# testduino.net
KiCad netlist of a schematic drawn in EAGLE
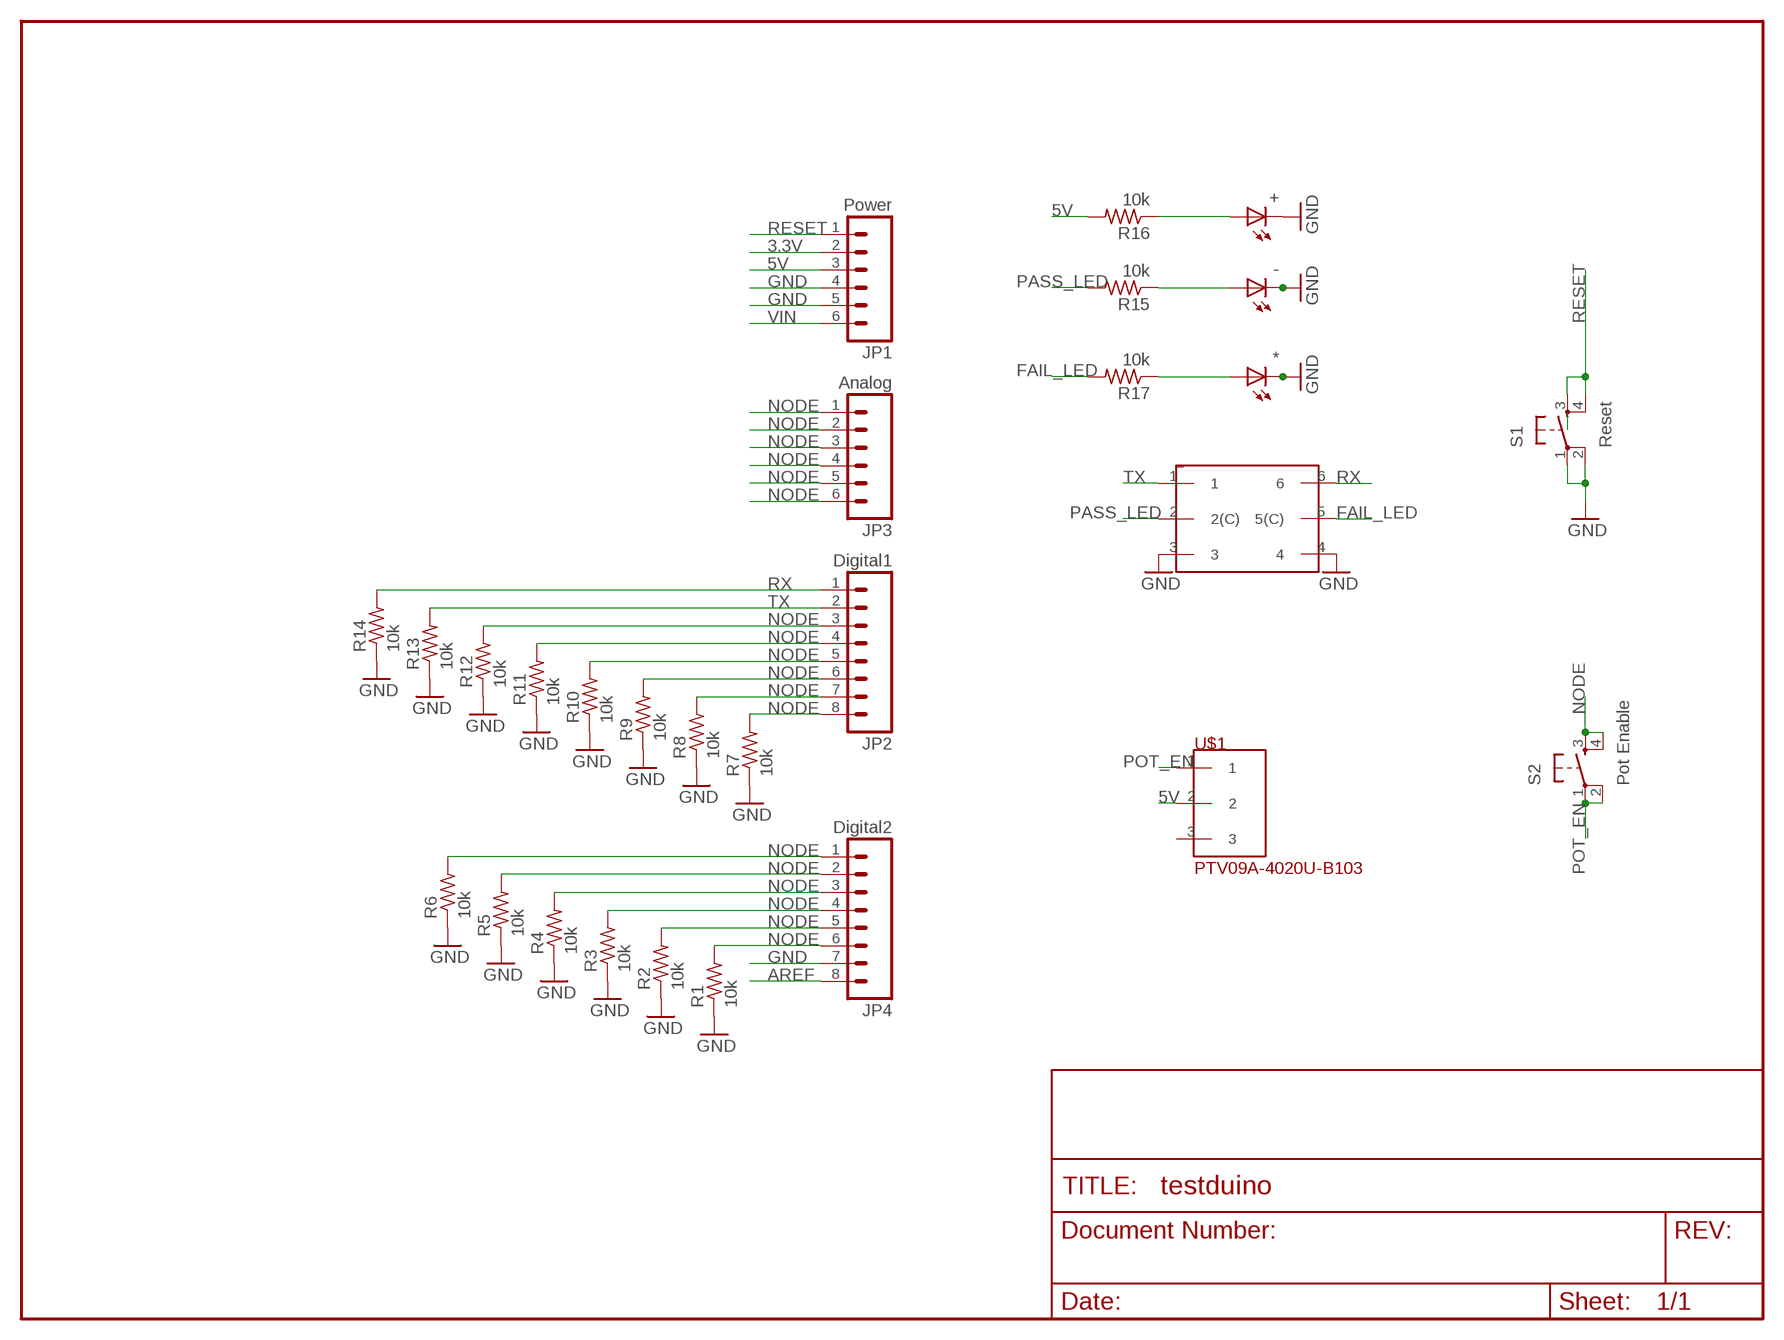
[diagram p0: schematic, sheet 1]

(export (version "E")
  (design (tool "Eeschema 10.0.6"))
  (components
    (comp (ref "*")
      (value "LEDSML0805")
      (footprint "eagle-import:SML0805")
      (libsource (lib "eagle-import") (part "LEDSML0805"))
    )
    (comp (ref "+")
      (value "LEDSML0805")
      (footprint "eagle-import:SML0805")
      (libsource (lib "eagle-import") (part "LEDSML0805"))
    )
    (comp (ref "-")
      (value "LEDSML0805")
      (footprint "eagle-import:SML0805")
      (libsource (lib "eagle-import") (part "LEDSML0805"))
    )
    (comp (ref "JP1")
      (value "Power")
      (footprint "eagle-import:1X06")
      (libsource (lib "eagle-import") (part "M06SIP"))
    )
    (comp (ref "JP2")
      (value "Digital1")
      (footprint "eagle-import:1X08")
      (libsource (lib "eagle-import") (part "M08"))
    )
    (comp (ref "JP3")
      (value "Analog")
      (footprint "eagle-import:1X06")
      (libsource (lib "eagle-import") (part "M06SIP"))
    )
    (comp (ref "JP4")
      (value "Digital2")
      (footprint "eagle-import:1X08")
      (libsource (lib "eagle-import") (part "M08"))
    )
    (comp (ref "R1")
      (value "10k")
      (footprint "eagle-import:R0402")
      (libsource (lib "eagle-import") (part "R-US_R0402"))
    )
    (comp (ref "R2")
      (value "10k")
      (footprint "eagle-import:R0402")
      (libsource (lib "eagle-import") (part "R-US_R0402"))
    )
    (comp (ref "R3")
      (value "10k")
      (footprint "eagle-import:R0402")
      (libsource (lib "eagle-import") (part "R-US_R0402"))
    )
    (comp (ref "R4")
      (value "10k")
      (footprint "eagle-import:R0402")
      (libsource (lib "eagle-import") (part "R-US_R0402"))
    )
    (comp (ref "R5")
      (value "10k")
      (footprint "eagle-import:R0402")
      (libsource (lib "eagle-import") (part "R-US_R0402"))
    )
    (comp (ref "R6")
      (value "10k")
      (footprint "eagle-import:R0402")
      (libsource (lib "eagle-import") (part "R-US_R0402"))
    )
    (comp (ref "R7")
      (value "10k")
      (footprint "eagle-import:R0402")
      (libsource (lib "eagle-import") (part "R-US_R0402"))
    )
    (comp (ref "R8")
      (value "10k")
      (footprint "eagle-import:R0402")
      (libsource (lib "eagle-import") (part "R-US_R0402"))
    )
    (comp (ref "R9")
      (value "10k")
      (footprint "eagle-import:R0402")
      (libsource (lib "eagle-import") (part "R-US_R0402"))
    )
    (comp (ref "R10")
      (value "10k")
      (footprint "eagle-import:R0402")
      (libsource (lib "eagle-import") (part "R-US_R0402"))
    )
    (comp (ref "R11")
      (value "10k")
      (footprint "eagle-import:R0402")
      (libsource (lib "eagle-import") (part "R-US_R0402"))
    )
    (comp (ref "R12")
      (value "10k")
      (footprint "eagle-import:R0402")
      (libsource (lib "eagle-import") (part "R-US_R0402"))
    )
    (comp (ref "R13")
      (value "10k")
      (footprint "eagle-import:R0402")
      (libsource (lib "eagle-import") (part "R-US_R0402"))
    )
    (comp (ref "R14")
      (value "10k")
      (footprint "eagle-import:R0402")
      (libsource (lib "eagle-import") (part "R-US_R0402"))
    )
    (comp (ref "R15")
      (value "10k")
      (footprint "eagle-import:R0402")
      (libsource (lib "eagle-import") (part "R-US_R0402"))
    )
    (comp (ref "R16")
      (value "10k")
      (footprint "eagle-import:R0402")
      (libsource (lib "eagle-import") (part "R-US_R0402"))
    )
    (comp (ref "R17")
      (value "10k")
      (footprint "eagle-import:R0402")
      (libsource (lib "eagle-import") (part "R-US_R0402"))
    )
    (comp (ref "S1")
      (value "Reset")
      (footprint "eagle-import:TACTILE-PTH")
      (libsource (lib "eagle-import") (part "TAC_SWITCHPTH"))
    )
    (comp (ref "S2")
      (value "Pot Enable")
      (footprint "eagle-import:TACTILE-PTH")
      (libsource (lib "eagle-import") (part "TAC_SWITCHPTH"))
    )
    (comp (ref "U$1")
      (value "PTV09A-4020U-B103")
      (footprint "eagle-import:PTV09A-1")
      (libsource (lib "eagle-import") (part "PTV09A-4020U-B103"))
    )
    (comp (ref "_")
      (value "JS202011SCQN")
      (footprint "eagle-import:JS202011SCQN")
      (libsource (lib "eagle-import") (part "JS202011SCQN"))
    )
  )
  (nets
    (net (code "1") (name "/3.3V") (class "Default")
      (node (ref "JP1") (pin "2") (pinfunction "2_2") (pintype "passive"))
    )
    (net (code "2") (name "/5V") (class "Default")
      (node (ref "JP1") (pin "3") (pinfunction "3_3") (pintype "passive"))
      (node (ref "R16") (pin "2") (pinfunction "2_2") (pintype "passive"))
      (node (ref "U$1") (pin "2") (pinfunction "2_2") (pintype "bidirectional"))
    )
    (net (code "3") (name "/AREF") (class "Default")
      (node (ref "JP4") (pin "8") (pinfunction "8_8") (pintype "passive"))
    )
    (net (code "4") (name "/FAIL_LED") (class "Default")
      (node (ref "R17") (pin "2") (pinfunction "2_2") (pintype "passive"))
      (node (ref "_") (pin "5") (pinfunction "5(C)_5") (pintype "bidirectional"))
    )
    (net (code "5") (name "/NODE") (class "Default")
      (node (ref "JP2") (pin "3") (pinfunction "3_3") (pintype "passive"))
      (node (ref "JP2") (pin "4") (pinfunction "4_4") (pintype "passive"))
      (node (ref "JP2") (pin "5") (pinfunction "5_5") (pintype "passive"))
      (node (ref "JP2") (pin "6") (pinfunction "6_6") (pintype "passive"))
      (node (ref "JP2") (pin "7") (pinfunction "7_7") (pintype "passive"))
      (node (ref "JP2") (pin "8") (pinfunction "8_8") (pintype "passive"))
      (node (ref "JP3") (pin "1") (pinfunction "1_1") (pintype "passive"))
      (node (ref "JP3") (pin "2") (pinfunction "2_2") (pintype "passive"))
      (node (ref "JP3") (pin "3") (pinfunction "3_3") (pintype "passive"))
      (node (ref "JP3") (pin "4") (pinfunction "4_4") (pintype "passive"))
      (node (ref "JP3") (pin "5") (pinfunction "5_5") (pintype "passive"))
      (node (ref "JP3") (pin "6") (pinfunction "6_6") (pintype "passive"))
      (node (ref "JP4") (pin "1") (pinfunction "1_1") (pintype "passive"))
      (node (ref "JP4") (pin "2") (pinfunction "2_2") (pintype "passive"))
      (node (ref "JP4") (pin "3") (pinfunction "3_3") (pintype "passive"))
      (node (ref "JP4") (pin "4") (pinfunction "4_4") (pintype "passive"))
      (node (ref "JP4") (pin "5") (pinfunction "5_5") (pintype "passive"))
      (node (ref "JP4") (pin "6") (pinfunction "6_6") (pintype "passive"))
      (node (ref "R1") (pin "2") (pinfunction "2_2") (pintype "passive"))
      (node (ref "R10") (pin "2") (pinfunction "2_2") (pintype "passive"))
      (node (ref "R11") (pin "2") (pinfunction "2_2") (pintype "passive"))
      (node (ref "R12") (pin "2") (pinfunction "2_2") (pintype "passive"))
      (node (ref "R2") (pin "2") (pinfunction "2_2") (pintype "passive"))
      (node (ref "R3") (pin "2") (pinfunction "2_2") (pintype "passive"))
      (node (ref "R4") (pin "2") (pinfunction "2_2") (pintype "passive"))
      (node (ref "R5") (pin "2") (pinfunction "2_2") (pintype "passive"))
      (node (ref "R6") (pin "2") (pinfunction "2_2") (pintype "passive"))
      (node (ref "R7") (pin "2") (pinfunction "2_2") (pintype "passive"))
      (node (ref "R8") (pin "2") (pinfunction "2_2") (pintype "passive"))
      (node (ref "R9") (pin "2") (pinfunction "2_2") (pintype "passive"))
      (node (ref "S2") (pin "3") (pinfunction "3_3") (pintype "passive"))
      (node (ref "S2") (pin "4") (pinfunction "4_4") (pintype "passive"))
    )
    (net (code "6") (name "/PASS_LED") (class "Default")
      (node (ref "R15") (pin "2") (pinfunction "2_2") (pintype "passive"))
      (node (ref "_") (pin "2") (pinfunction "2(C)_2") (pintype "bidirectional"))
    )
    (net (code "7") (name "/POT_EN") (class "Default")
      (node (ref "S2") (pin "1") (pinfunction "1_1") (pintype "passive"))
      (node (ref "S2") (pin "2") (pinfunction "2_2") (pintype "passive"))
      (node (ref "U$1") (pin "1") (pinfunction "1_1") (pintype "bidirectional"))
    )
    (net (code "8") (name "/RESET") (class "Default")
      (node (ref "JP1") (pin "1") (pinfunction "1_1") (pintype "passive"))
      (node (ref "S1") (pin "3") (pinfunction "3_3") (pintype "passive"))
      (node (ref "S1") (pin "4") (pinfunction "4_4") (pintype "passive"))
    )
    (net (code "9") (name "/RX") (class "Default")
      (node (ref "JP2") (pin "1") (pinfunction "1_1") (pintype "passive"))
      (node (ref "R14") (pin "2") (pinfunction "2_2") (pintype "passive"))
      (node (ref "_") (pin "6") (pinfunction "6_6") (pintype "bidirectional"))
    )
    (net (code "10") (name "/TX") (class "Default")
      (node (ref "JP2") (pin "2") (pinfunction "2_2") (pintype "passive"))
      (node (ref "R13") (pin "2") (pinfunction "2_2") (pintype "passive"))
      (node (ref "_") (pin "1") (pinfunction "1_1") (pintype "bidirectional"))
    )
    (net (code "11") (name "/VIN") (class "Default")
      (node (ref "JP1") (pin "6") (pinfunction "6_6") (pintype "passive"))
    )
    (net (code "12") (name "GND") (class "Default")
      (node (ref "*") (pin "C") (pinfunction "C_C") (pintype "passive"))
      (node (ref "+") (pin "C") (pinfunction "C_C") (pintype "passive"))
      (node (ref "-") (pin "C") (pinfunction "C_C") (pintype "passive"))
      (node (ref "JP1") (pin "4") (pinfunction "4_4") (pintype "passive"))
      (node (ref "JP1") (pin "5") (pinfunction "5_5") (pintype "passive"))
      (node (ref "JP4") (pin "7") (pinfunction "7_7") (pintype "passive"))
      (node (ref "R1") (pin "1") (pinfunction "1_1") (pintype "passive"))
      (node (ref "R10") (pin "1") (pinfunction "1_1") (pintype "passive"))
      (node (ref "R11") (pin "1") (pinfunction "1_1") (pintype "passive"))
      (node (ref "R12") (pin "1") (pinfunction "1_1") (pintype "passive"))
      (node (ref "R13") (pin "1") (pinfunction "1_1") (pintype "passive"))
      (node (ref "R14") (pin "1") (pinfunction "1_1") (pintype "passive"))
      (node (ref "R2") (pin "1") (pinfunction "1_1") (pintype "passive"))
      (node (ref "R3") (pin "1") (pinfunction "1_1") (pintype "passive"))
      (node (ref "R4") (pin "1") (pinfunction "1_1") (pintype "passive"))
      (node (ref "R5") (pin "1") (pinfunction "1_1") (pintype "passive"))
      (node (ref "R6") (pin "1") (pinfunction "1_1") (pintype "passive"))
      (node (ref "R7") (pin "1") (pinfunction "1_1") (pintype "passive"))
      (node (ref "R8") (pin "1") (pinfunction "1_1") (pintype "passive"))
      (node (ref "R9") (pin "1") (pinfunction "1_1") (pintype "passive"))
      (node (ref "S1") (pin "1") (pinfunction "1_1") (pintype "passive"))
      (node (ref "S1") (pin "2") (pinfunction "2_2") (pintype "passive"))
      (node (ref "_") (pin "3") (pinfunction "3_3") (pintype "bidirectional"))
      (node (ref "_") (pin "4") (pinfunction "4_4") (pintype "bidirectional"))
    )
    (net (code "13") (name "Net-(*-PadA)") (class "Default")
      (node (ref "*") (pin "A") (pinfunction "A_A") (pintype "passive"))
      (node (ref "R17") (pin "1") (pinfunction "1_1") (pintype "passive"))
    )
    (net (code "14") (name "Net-(+-PadA)") (class "Default")
      (node (ref "+") (pin "A") (pinfunction "A_A") (pintype "passive"))
      (node (ref "R16") (pin "1") (pinfunction "1_1") (pintype "passive"))
    )
    (net (code "15") (name "Net-(--PadA)") (class "Default")
      (node (ref "-") (pin "A") (pinfunction "A_A") (pintype "passive"))
      (node (ref "R15") (pin "1") (pinfunction "1_1") (pintype "passive"))
    )
    (net (code "16") (name "unconnected-(U$1-Pad3)") (class "Default")
      (node (ref "U$1") (pin "3") (pinfunction "3_3") (pintype "bidirectional"))
    )
  )
)
